# 5VPart.net
KiCad netlist of a schematic drawn in EAGLE
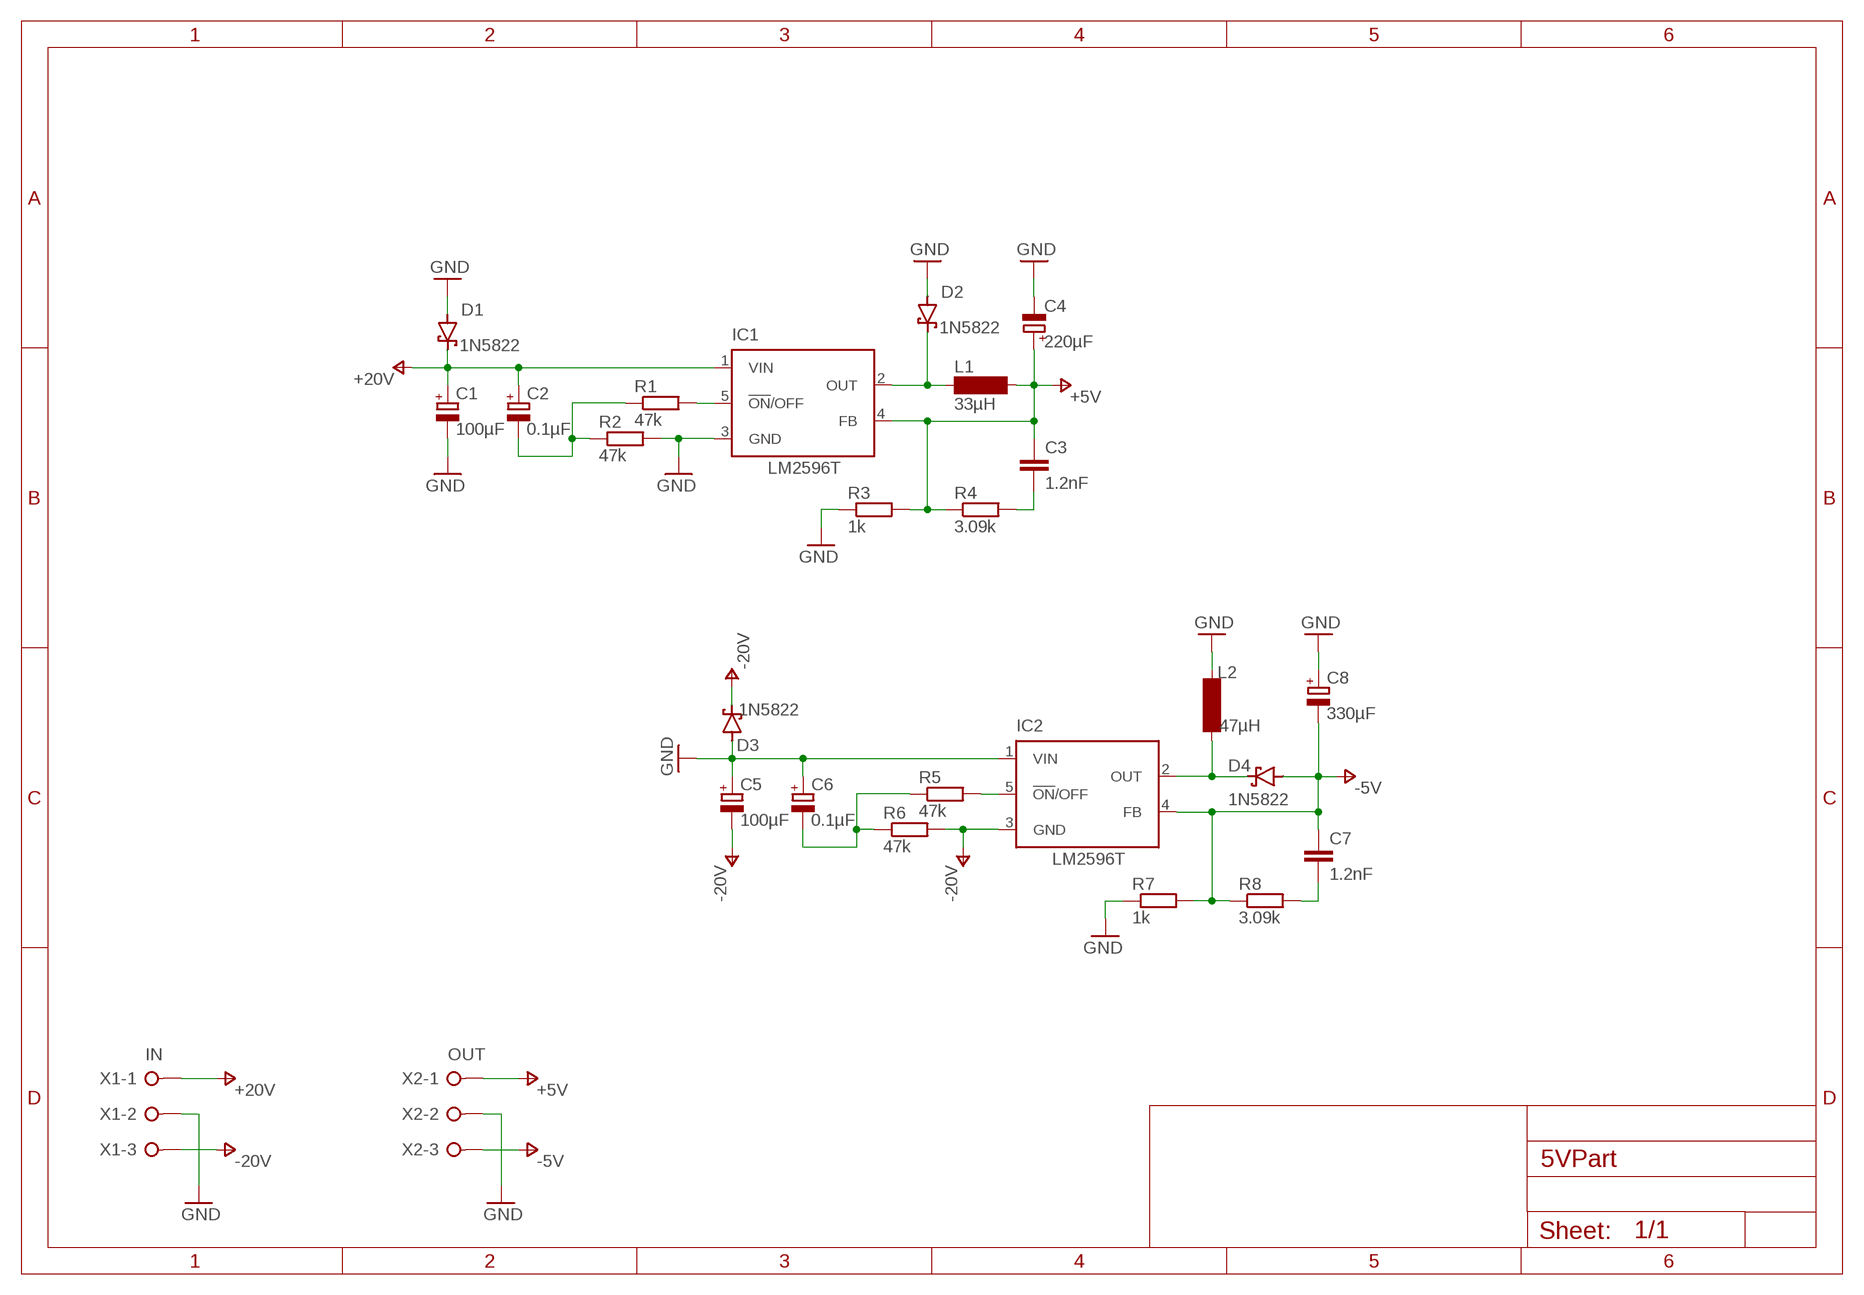
[diagram p0: schematic, sheet 1]

(export (version "E")
  (design (tool "Eeschema 10.0.6"))
  (components
    (comp (ref "C1")
      (value "100µF")
      (footprint "eagle-import:E2,5-6")
      (libsource (lib "eagle-import") (part "CPOL-EUE2.5-6"))
    )
    (comp (ref "C2")
      (value "0.1µF")
      (footprint "eagle-import:E1,8-4")
      (libsource (lib "eagle-import") (part "CPOL-EUE1.8-4"))
    )
    (comp (ref "C3")
      (value "1.2nF")
      (footprint "eagle-import:C050-024X044")
      (libsource (lib "eagle-import") (part "C-EU050-024X044"))
    )
    (comp (ref "C4")
      (value "220µF")
      (footprint "eagle-import:E3,5-8")
      (libsource (lib "eagle-import") (part "CPOL-EUE3.5-8"))
    )
    (comp (ref "C5")
      (value "100µF")
      (footprint "eagle-import:E2,5-6")
      (libsource (lib "eagle-import") (part "CPOL-EUE2.5-6"))
    )
    (comp (ref "C6")
      (value "0.1µF")
      (footprint "eagle-import:E1,8-4")
      (libsource (lib "eagle-import") (part "CPOL-EUE1.8-4"))
    )
    (comp (ref "C7")
      (value "1.2nF")
      (footprint "eagle-import:C050-024X044")
      (libsource (lib "eagle-import") (part "C-EU050-024X044"))
    )
    (comp (ref "C8")
      (value "330µF")
      (footprint "eagle-import:E3,5-8")
      (libsource (lib "eagle-import") (part "CPOL-EUE3.5-8"))
    )
    (comp (ref "D1")
      (value "1N5822")
      (footprint "eagle-import:C4111-15")
      (libsource (lib "eagle-import") (part "SCHOTTKY-DIODEC4111-15"))
    )
    (comp (ref "D2")
      (value "1N5822")
      (footprint "eagle-import:C4111-15")
      (libsource (lib "eagle-import") (part "SCHOTTKY-DIODEC4111-15"))
    )
    (comp (ref "D3")
      (value "1N5822")
      (footprint "eagle-import:C4111-15")
      (libsource (lib "eagle-import") (part "SCHOTTKY-DIODEC4111-15"))
    )
    (comp (ref "D4")
      (value "1N5822")
      (footprint "eagle-import:C4111-15")
      (libsource (lib "eagle-import") (part "SCHOTTKY-DIODEC4111-15"))
    )
    (comp (ref "IC1")
      (value "LM2596T")
      (footprint "eagle-import:T05D")
      (fields (field (name "MPN") "LM2596T-ADJ/LF02"))
      (libsource (lib "eagle-import") (part "LM2596T"))
    )
    (comp (ref "IC2")
      (value "LM2596T")
      (footprint "eagle-import:T05D")
      (fields (field (name "MPN") "LM2596T-ADJ/LF02"))
      (libsource (lib "eagle-import") (part "LM2596T"))
    )
    (comp (ref "L1")
      (value "33µH")
      (footprint "eagle-import:SD12-680")
      (fields (field (name "MF") "BUSSMANN") (field (name "MPN") "SD12-680"))
      (libsource (lib "eagle-import") (part "SD12-680"))
    )
    (comp (ref "L2")
      (value "47µH")
      (footprint "eagle-import:SD12-680")
      (fields (field (name "MF") "BUSSMANN") (field (name "MPN") "SD12-680"))
      (libsource (lib "eagle-import") (part "SD12-680"))
    )
    (comp (ref "R1")
      (value "47k")
      (footprint "eagle-import:0207_10")
      (libsource (lib "eagle-import") (part "R-EU_0207/10"))
    )
    (comp (ref "R2")
      (value "47k")
      (footprint "eagle-import:0207_10")
      (libsource (lib "eagle-import") (part "R-EU_0207/10"))
    )
    (comp (ref "R3")
      (value "1k")
      (footprint "eagle-import:0207_10")
      (libsource (lib "eagle-import") (part "R-EU_0207/10"))
    )
    (comp (ref "R4")
      (value "3.09k")
      (footprint "eagle-import:0207_10")
      (libsource (lib "eagle-import") (part "R-EU_0207/10"))
    )
    (comp (ref "R5")
      (value "47k")
      (footprint "eagle-import:0207_10")
      (libsource (lib "eagle-import") (part "R-EU_0207/10"))
    )
    (comp (ref "R6")
      (value "47k")
      (footprint "eagle-import:0207_10")
      (libsource (lib "eagle-import") (part "R-EU_0207/10"))
    )
    (comp (ref "R7")
      (value "1k")
      (footprint "eagle-import:0207_10")
      (libsource (lib "eagle-import") (part "R-EU_0207/10"))
    )
    (comp (ref "R8")
      (value "3.09k")
      (footprint "eagle-import:0207_10")
      (libsource (lib "eagle-import") (part "R-EU_0207/10"))
    )
    (comp (ref "X1")
      (value "IN")
      (footprint "eagle-import:W237-133")
      (libsource (lib "eagle-import") (part "W237-03P"))
    )
    (comp (ref "X2")
      (value "OUT")
      (footprint "eagle-import:W237-133")
      (libsource (lib "eagle-import") (part "W237-03P"))
    )
  )
  (nets
    (net (code "1") (name "+5V") (class "Default")
      (node (ref "C3") (pin "1") (pinfunction "1_1") (pintype "passive"))
      (node (ref "C4") (pin "+") (pinfunction "+_+") (pintype "passive"))
      (node (ref "IC1") (pin "4") (pinfunction "FB_4") (pintype "input"))
      (node (ref "L1") (pin "2") (pinfunction "2_2") (pintype "passive"))
      (node (ref "R3") (pin "2") (pinfunction "2_2") (pintype "passive"))
      (node (ref "R4") (pin "1") (pinfunction "1_1") (pintype "passive"))
      (node (ref "X2") (pin "1") (pinfunction "KL_1") (pintype "passive"))
    )
    (net (code "2") (name "+20V") (class "Default")
      (node (ref "C1") (pin "+") (pinfunction "+_+") (pintype "passive"))
      (node (ref "C2") (pin "+") (pinfunction "+_+") (pintype "passive"))
      (node (ref "D1") (pin "C") (pinfunction "C_C") (pintype "passive"))
      (node (ref "IC1") (pin "1") (pinfunction "VIN_1") (pintype "input"))
      (node (ref "X1") (pin "1") (pinfunction "KL_1") (pintype "passive"))
    )
    (net (code "3") (name "-5V") (class "Default")
      (node (ref "C7") (pin "1") (pinfunction "1_1") (pintype "passive"))
      (node (ref "C8") (pin "-") (pinfunction "-_-") (pintype "passive"))
      (node (ref "D4") (pin "A") (pinfunction "A_A") (pintype "passive"))
      (node (ref "IC2") (pin "4") (pinfunction "FB_4") (pintype "input"))
      (node (ref "R7") (pin "2") (pinfunction "2_2") (pintype "passive"))
      (node (ref "R8") (pin "1") (pinfunction "1_1") (pintype "passive"))
      (node (ref "X2") (pin "3") (pinfunction "KL_3") (pintype "passive"))
    )
    (net (code "4") (name "-20V") (class "Default")
      (node (ref "C5") (pin "-") (pinfunction "-_-") (pintype "passive"))
      (node (ref "D3") (pin "C") (pinfunction "C_C") (pintype "passive"))
      (node (ref "IC2") (pin "3") (pinfunction "GND_3") (pintype "power_in"))
      (node (ref "R6") (pin "2") (pinfunction "2_2") (pintype "passive"))
      (node (ref "X1") (pin "3") (pinfunction "KL_3") (pintype "passive"))
    )
    (net (code "5") (name "GND") (class "Default")
      (node (ref "C1") (pin "-") (pinfunction "-_-") (pintype "passive"))
      (node (ref "C4") (pin "-") (pinfunction "-_-") (pintype "passive"))
      (node (ref "C5") (pin "+") (pinfunction "+_+") (pintype "passive"))
      (node (ref "C6") (pin "+") (pinfunction "+_+") (pintype "passive"))
      (node (ref "C8") (pin "+") (pinfunction "+_+") (pintype "passive"))
      (node (ref "D1") (pin "A") (pinfunction "A_A") (pintype "passive"))
      (node (ref "D2") (pin "A") (pinfunction "A_A") (pintype "passive"))
      (node (ref "D3") (pin "A") (pinfunction "A_A") (pintype "passive"))
      (node (ref "IC1") (pin "3") (pinfunction "GND_3") (pintype "power_in"))
      (node (ref "IC2") (pin "1") (pinfunction "VIN_1") (pintype "input"))
      (node (ref "L2") (pin "2") (pinfunction "2_2") (pintype "passive"))
      (node (ref "R2") (pin "2") (pinfunction "2_2") (pintype "passive"))
      (node (ref "R3") (pin "1") (pinfunction "1_1") (pintype "passive"))
      (node (ref "R7") (pin "1") (pinfunction "1_1") (pintype "passive"))
      (node (ref "X1") (pin "2") (pinfunction "KL_2") (pintype "passive"))
      (node (ref "X2") (pin "2") (pinfunction "KL_2") (pintype "passive"))
    )
    (net (code "6") (name "Net-(C2-Pad-)") (class "Default")
      (node (ref "C2") (pin "-") (pinfunction "-_-") (pintype "passive"))
      (node (ref "R1") (pin "1") (pinfunction "1_1") (pintype "passive"))
      (node (ref "R2") (pin "1") (pinfunction "1_1") (pintype "passive"))
    )
    (net (code "7") (name "Net-(C3-Pad2)") (class "Default")
      (node (ref "C3") (pin "2") (pinfunction "2_2") (pintype "passive"))
      (node (ref "R4") (pin "2") (pinfunction "2_2") (pintype "passive"))
    )
    (net (code "8") (name "Net-(C6-Pad-)") (class "Default")
      (node (ref "C6") (pin "-") (pinfunction "-_-") (pintype "passive"))
      (node (ref "R5") (pin "1") (pinfunction "1_1") (pintype "passive"))
      (node (ref "R6") (pin "1") (pinfunction "1_1") (pintype "passive"))
    )
    (net (code "9") (name "Net-(C7-Pad2)") (class "Default")
      (node (ref "C7") (pin "2") (pinfunction "2_2") (pintype "passive"))
      (node (ref "R8") (pin "2") (pinfunction "2_2") (pintype "passive"))
    )
    (net (code "10") (name "Net-(IC1-OUT)") (class "Default")
      (node (ref "D2") (pin "C") (pinfunction "C_C") (pintype "passive"))
      (node (ref "IC1") (pin "2") (pinfunction "OUT_2") (pintype "output"))
      (node (ref "L1") (pin "1") (pinfunction "1_1") (pintype "passive"))
    )
    (net (code "11") (name "Net-(IC1-~{ON}{slash}OFF)") (class "Default")
      (node (ref "IC1") (pin "5") (pinfunction "~{ON}/OFF_5") (pintype "input"))
      (node (ref "R1") (pin "2") (pinfunction "2_2") (pintype "passive"))
    )
    (net (code "12") (name "Net-(IC2-OUT)") (class "Default")
      (node (ref "D4") (pin "C") (pinfunction "C_C") (pintype "passive"))
      (node (ref "IC2") (pin "2") (pinfunction "OUT_2") (pintype "output"))
      (node (ref "L2") (pin "1") (pinfunction "1_1") (pintype "passive"))
    )
    (net (code "13") (name "Net-(IC2-~{ON}{slash}OFF)") (class "Default")
      (node (ref "IC2") (pin "5") (pinfunction "~{ON}/OFF_5") (pintype "input"))
      (node (ref "R5") (pin "2") (pinfunction "2_2") (pintype "passive"))
    )
  )
)
